# OLED096.net
KiCad netlist of a schematic drawn in Altium Designer
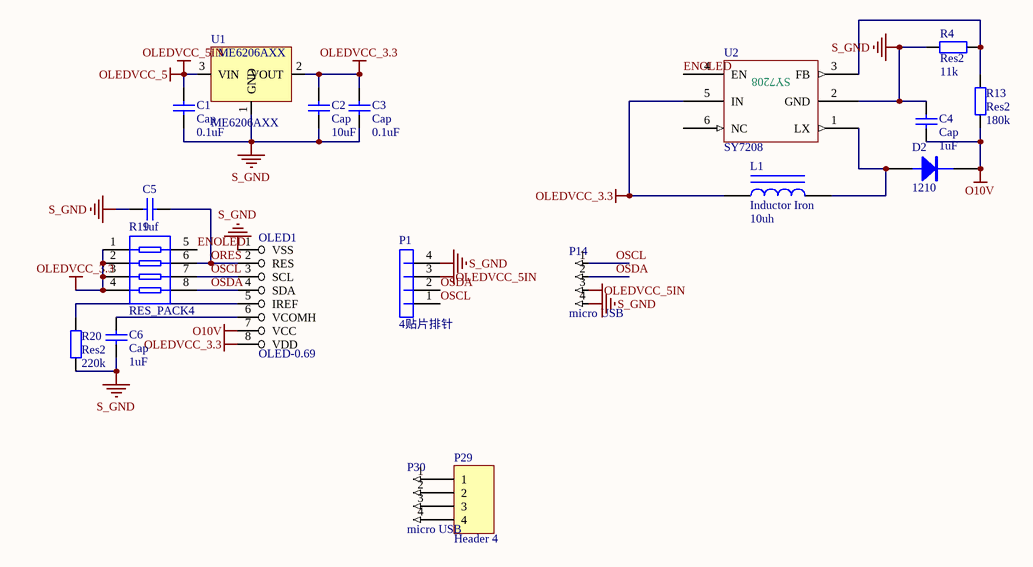
[diagram p0: OLED096.SchDoc]

(export (version "E")
  (design (tool "Eeschema 10.0.6"))
  (components
    (comp (ref "C1")
      (value "Cap")
      (footprint "6-0805")
      (description "Capacitor")
      (fields (field (name "ALTIUM_VALUE") "0.1uF") (field (name "PUBLISHER") "Altium Limited"))
      (libsource (lib "Miscellaneous Devices") (part "Cap"))
    )
    (comp (ref "C2")
      (value "Cap")
      (footprint "6-0805")
      (description "Capacitor")
      (fields (field (name "ALTIUM_VALUE") "10uF") (field (name "PUBLISHER") "Altium Limited"))
      (libsource (lib "Miscellaneous Devices") (part "Cap"))
    )
    (comp (ref "C3")
      (value "Cap")
      (footprint "6-0805")
      (description "Capacitor")
      (fields (field (name "ALTIUM_VALUE") "0.1uF") (field (name "PUBLISHER") "Altium Limited"))
      (libsource (lib "Miscellaneous Devices") (part "Cap"))
    )
    (comp (ref "C4")
      (value "Cap")
      (footprint "LC-0603_C")
      (description "Capacitor")
      (fields (field (name "ALTIUM_VALUE") "1uF") (field (name "PUBLISHER") "Altium Limited"))
      (libsource (lib "Miscellaneous Devices") (part "Cap"))
    )
    (comp (ref "C5")
      (value "1uf")
      (footprint "LC-0603_C")
      (description "Capacitor")
      (fields (field (name "Comment") "Cap") (field (name "PUBLISHER") "Altium Limited"))
      (libsource (lib "Miscellaneous Devices") (part "Cap"))
    )
    (comp (ref "C6")
      (value "Cap")
      (footprint "LC-0603_C")
      (description "Capacitor")
      (fields (field (name "ALTIUM_VALUE") "1uF") (field (name "PUBLISHER") "Altium Limited"))
      (libsource (lib "Miscellaneous Devices") (part "Cap"))
    )
    (comp (ref "D2") (value "1210") (footprint "LC-1206_L") (libsource (lib "ARAMYLIB") (part "1N4001")))
    (comp (ref "L1")
      (value "Inductor Iron")
      (footprint "LC-0805_L")
      (description "Magnetic-Core Inductor")
      (fields (field (name "ALTIUM_VALUE") "10uh") (field (name "PUBLISHER") "Altium Limited"))
      (libsource (lib "Miscellaneous Devices") (part "Inductor Iron"))
    )
    (comp (ref "OLED1")
      (value "OLED-0.69")
      (footprint "OLED-0.69")
      (libsource (lib "ARAMYLIB") (part "OLED-0.69"))
    )
    (comp (ref "P1") (value "4贴片排针") (footprint "4针贴片接头2.0") (libsource (lib "ARAMYLIB") (part "4贴片排针")))
    (comp (ref "P14")
      (value "micro USB")
      (footprint "1.0MM 翻盖 下接 FPC连接器 4P")
      (libsource (lib "ros_car_lib") (part "FPC 4P 1MM"))
    )
    (comp (ref "P29")
      (value "Header 4")
      (footprint "HDR1X4")
      (description "Header, 4-Pin")
      (fields (field (name "PUBLISHER") "Altium Limited"))
      (libsource (lib "Miscellaneous Connectors") (part "Header 4"))
    )
    (comp (ref "P30")
      (value "micro USB")
      (footprint "1.0MM 翻盖 下接 FPC连接器 4P")
      (libsource (lib "ros_car_lib") (part "FPC 4P 1MM"))
    )
    (comp (ref "R4")
      (value "Res2")
      (footprint "LC-0603_R")
      (description "Resistor")
      (fields (field (name "ALTIUM_VALUE") "11k") (field (name "PUBLISHER") "Altium Limited"))
      (libsource (lib "") (part "Res2_1"))
    )
    (comp (ref "R13")
      (value "Res2")
      (footprint "LC-0603_R")
      (description "Resistor")
      (fields (field (name "ALTIUM_VALUE") "180k") (field (name "PUBLISHER") "Altium Limited"))
      (libsource (lib "Miscellaneous Devices") (part "Res2"))
    )
    (comp (ref "R19") (value "RES_PACK4") (footprint "RES4") (libsource (lib "ARAMYLIB") (part "RES_PACK4")))
    (comp (ref "R20")
      (value "Res2")
      (footprint "LC-0603_R")
      (description "Resistor")
      (fields (field (name "ALTIUM_VALUE") "220k") (field (name "PUBLISHER") "Altium Limited"))
      (libsource (lib "Miscellaneous Devices") (part "Res2"))
    )
    (comp (ref "U1") (value "ME6206AXX") (footprint "sot23") (libsource (lib "ARAMY_四轴") (part "ME6206AXX")))
    (comp (ref "U2") (value "SY7208") (footprint "LC-SOT-23-6") (libsource (lib "ARAMYLIB") (part "SY7208")))
  )
  (nets
    (net (code "1") (name "/ENOLED") (class "Default")
      (node (ref "R19") (pin "5") (pinfunction "5_5") (pintype "passive"))
      (node (ref "U2") (pin "4") (pinfunction "EN_4") (pintype "power_in"))
    )
    (net (code "2") (name "/ORES") (class "Default")
      (node (ref "C5") (pin "2") (pinfunction "2_2") (pintype "passive"))
      (node (ref "OLED1") (pin "2") (pinfunction "RES_2") (pintype "passive"))
      (node (ref "R19") (pin "6") (pinfunction "6_6") (pintype "passive"))
    )
    (net (code "3") (name "/OSCL") (class "Default")
      (node (ref "OLED1") (pin "3") (pinfunction "SCL_3") (pintype "passive"))
      (node (ref "P1") (pin "1") (pinfunction "1_1") (pintype "passive"))
      (node (ref "P14") (pin "1") (pinfunction "1_1") (pintype "input"))
      (node (ref "R19") (pin "7") (pinfunction "7_7") (pintype "passive"))
    )
    (net (code "4") (name "/OSDA") (class "Default")
      (node (ref "OLED1") (pin "4") (pinfunction "SDA_4") (pintype "passive"))
      (node (ref "P1") (pin "2") (pinfunction "2_2") (pintype "passive"))
      (node (ref "P14") (pin "2") (pinfunction "2_2") (pintype "input"))
      (node (ref "R19") (pin "8") (pinfunction "8_8") (pintype "passive"))
    )
    (net (code "5") (name "Net-(D2-1)") (class "Default")
      (node (ref "D2") (pin "A") (pinfunction "1_A") (pintype "passive"))
      (node (ref "L1") (pin "2") (pinfunction "2_2") (pintype "passive"))
      (node (ref "U2") (pin "1") (pinfunction "LX_1") (pintype "output"))
    )
    (net (code "6") (name "Net-(OLED1-IREF)") (class "Default")
      (node (ref "OLED1") (pin "5") (pinfunction "IREF_5") (pintype "passive"))
      (node (ref "R20") (pin "2") (pinfunction "2_2") (pintype "passive"))
    )
    (net (code "7") (name "Net-(OLED1-VCOMH)") (class "Default")
      (node (ref "C6") (pin "1") (pinfunction "1_1") (pintype "passive"))
      (node (ref "OLED1") (pin "6") (pinfunction "VCOMH_6") (pintype "passive"))
    )
    (net (code "8") (name "Net-(P29-Pad1)") (class "Default")
      (node (ref "P29") (pin "1") (pinfunction "1_1") (pintype "passive"))
      (node (ref "P30") (pin "1") (pinfunction "1_1") (pintype "input"))
    )
    (net (code "9") (name "Net-(P29-Pad2)") (class "Default")
      (node (ref "P29") (pin "2") (pinfunction "2_2") (pintype "passive"))
      (node (ref "P30") (pin "2") (pinfunction "2_2") (pintype "input"))
    )
    (net (code "10") (name "Net-(P29-Pad3)") (class "Default")
      (node (ref "P29") (pin "3") (pinfunction "3_3") (pintype "passive"))
      (node (ref "P30") (pin "3") (pinfunction "3_3") (pintype "input"))
    )
    (net (code "11") (name "Net-(P29-Pad4)") (class "Default")
      (node (ref "P29") (pin "4") (pinfunction "4_4") (pintype "passive"))
      (node (ref "P30") (pin "4") (pinfunction "4_4") (pintype "input"))
    )
    (net (code "12") (name "Net-(U2-FB)") (class "Default")
      (node (ref "R13") (pin "2") (pinfunction "2_2") (pintype "passive"))
      (node (ref "R4") (pin "1") (pinfunction "1_1") (pintype "passive"))
      (node (ref "U2") (pin "3") (pinfunction "FB_3") (pintype "output"))
    )
    (net (code "13") (name "O10V") (class "Default")
      (node (ref "C4") (pin "1") (pinfunction "1_1") (pintype "passive"))
      (node (ref "D2") (pin "K") (pinfunction "2_K") (pintype "passive"))
      (node (ref "OLED1") (pin "7") (pinfunction "VCC_7") (pintype "power_in"))
      (node (ref "R13") (pin "1") (pinfunction "1_1") (pintype "passive"))
    )
    (net (code "14") (name "OLEDVCC_3.3") (class "Default")
      (node (ref "C2") (pin "1") (pinfunction "1_1") (pintype "passive"))
      (node (ref "C3") (pin "1") (pinfunction "1_1") (pintype "passive"))
      (node (ref "L1") (pin "1") (pinfunction "1_1") (pintype "passive"))
      (node (ref "OLED1") (pin "8") (pinfunction "VDD_8") (pintype "power_in"))
      (node (ref "R19") (pin "1") (pinfunction "1_1") (pintype "passive"))
      (node (ref "R19") (pin "2") (pinfunction "2_2") (pintype "passive"))
      (node (ref "R19") (pin "3") (pinfunction "3_3") (pintype "passive"))
      (node (ref "R19") (pin "4") (pinfunction "4_4") (pintype "passive"))
      (node (ref "U1") (pin "2") (pinfunction "VOUT_2") (pintype "passive"))
      (node (ref "U2") (pin "5") (pinfunction "IN_5") (pintype "power_in"))
    )
    (net (code "15") (name "OLEDVCC_5") (class "Default")
      (node (ref "C1") (pin "1") (pinfunction "1_1") (pintype "passive"))
      (node (ref "P1") (pin "3") (pinfunction "3_3") (pintype "passive"))
      (node (ref "P14") (pin "3") (pinfunction "3_3") (pintype "input"))
      (node (ref "U1") (pin "3") (pinfunction "VIN_3") (pintype "power_in"))
    )
    (net (code "16") (name "S_GND") (class "Default")
      (node (ref "C1") (pin "2") (pinfunction "2_2") (pintype "passive"))
      (node (ref "C2") (pin "2") (pinfunction "2_2") (pintype "passive"))
      (node (ref "C3") (pin "2") (pinfunction "2_2") (pintype "passive"))
      (node (ref "C4") (pin "2") (pinfunction "2_2") (pintype "passive"))
      (node (ref "C5") (pin "1") (pinfunction "1_1") (pintype "passive"))
      (node (ref "C6") (pin "2") (pinfunction "2_2") (pintype "passive"))
      (node (ref "OLED1") (pin "1") (pinfunction "VSS_1") (pintype "power_in"))
      (node (ref "P1") (pin "4") (pinfunction "4_4") (pintype "passive"))
      (node (ref "P14") (pin "4") (pinfunction "4_4") (pintype "input"))
      (node (ref "R20") (pin "1") (pinfunction "1_1") (pintype "passive"))
      (node (ref "R4") (pin "2") (pinfunction "2_2") (pintype "passive"))
      (node (ref "U1") (pin "1") (pinfunction "GND_1") (pintype "power_in"))
      (node (ref "U2") (pin "2") (pinfunction "GND_2") (pintype "power_in"))
    )
    (net (code "17") (name "unconnected-(U2-NC-Pad6)") (class "Default")
      (node (ref "U2") (pin "6") (pinfunction "NC_6") (pintype "input"))
    )
  )
)
